# cartridge.net
KiCad netlist of a schematic drawn in EasyEDA Pro
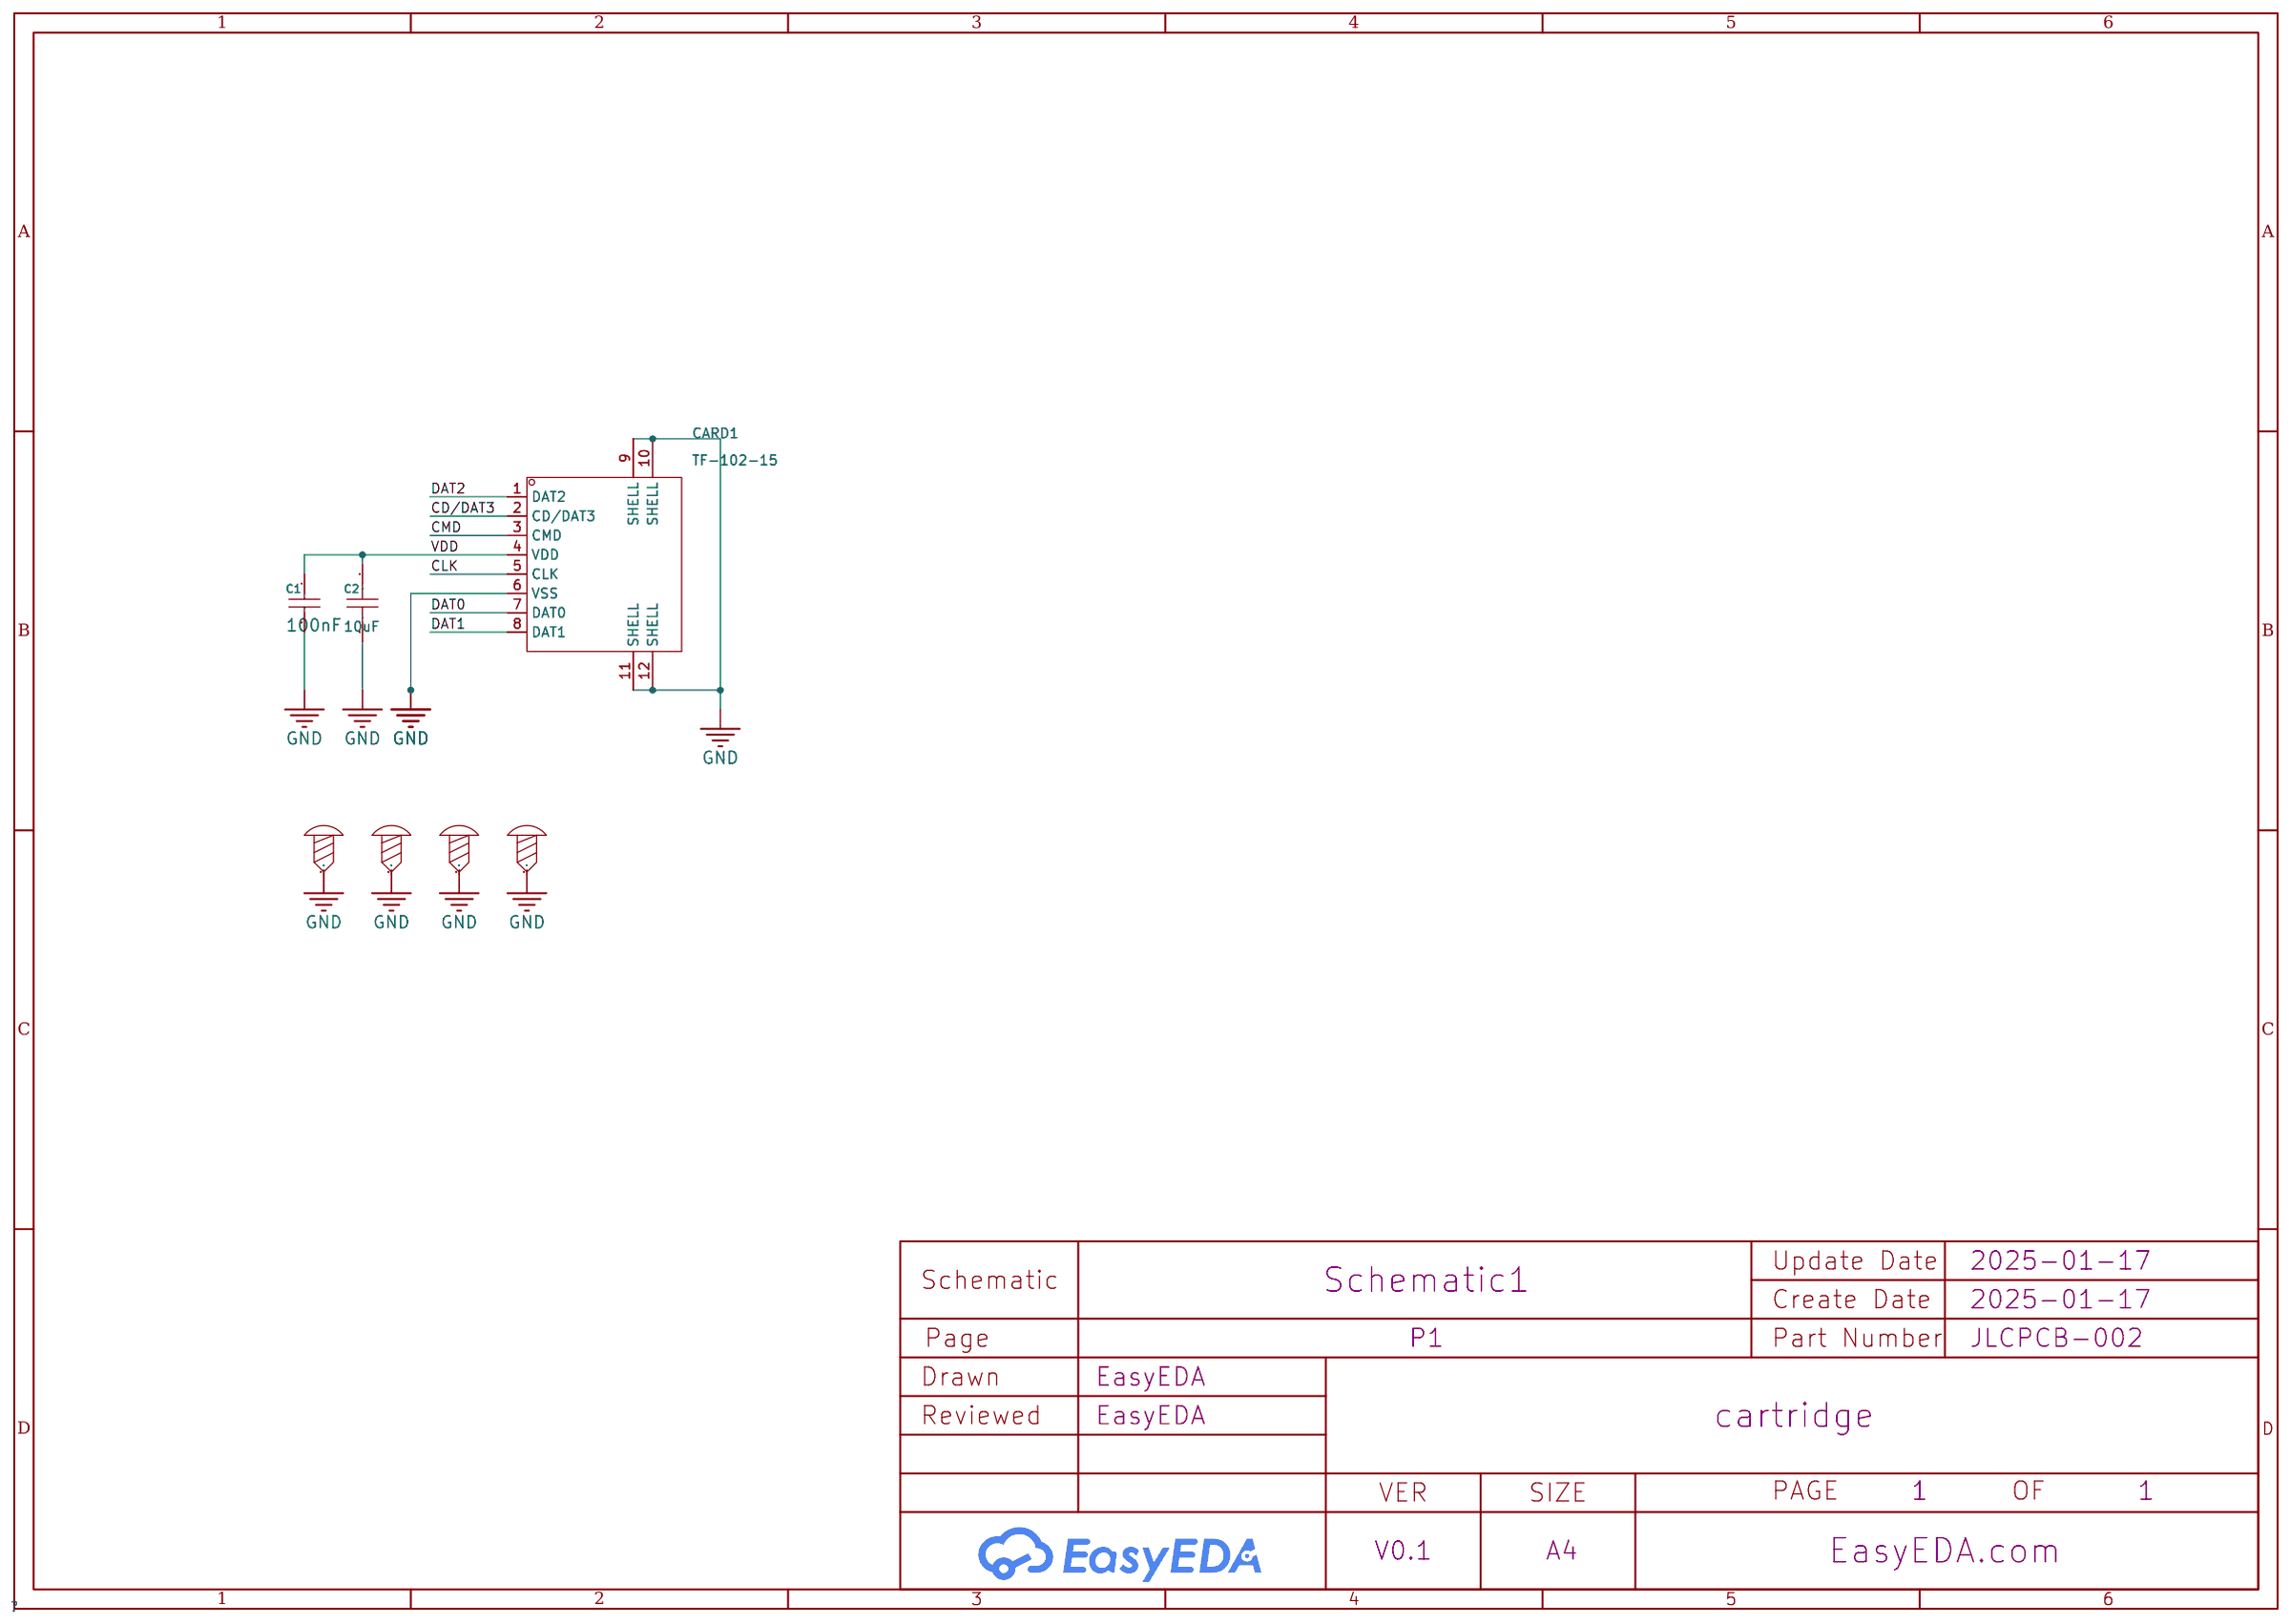
[diagram p0: schematic sheet]

(export (version "E")
  (design (tool "Eeschema 10.0.6"))
  (components
    (comp (ref "C1")
      (value "100nF")
      (footprint "easyedapro:C0805")
      (fields
        (field (name "Manufacturer Part") "CL21B104KBCNNNC")
        (field (name "Manufacturer") "SAMSUNG(三星)")
      )
      (libsource (lib "easyedapro") (part "CL21B104KBCNNNC"))
    )
    (comp (ref "C2")
      (value "10uF")
      (footprint "easyedapro:C0805")
      (fields
        (field (name "Manufacturer Part") "CL21A106KAYNNNE")
        (field (name "Manufacturer") "SAMSUNG(三星)")
      )
      (libsource (lib "easyedapro") (part "CL21A106KAYNNNE"))
    )
    (comp (ref "CARD1")
      (value "TF-102-15")
      (footprint "easyedapro:TF-SMD_TF-102-15")
      (fields (field (name "Manufacturer") "XUNPU(讯普)"))
      (libsource (lib "easyedapro") (part "TF-102-15"))
    )
    (comp (ref "SCREW1")
      (value "~")
      (footprint "easyedapro:Screw-Hole-M2")
      (libsource (lib "easyedapro") (part "Screw-Hole"))
    )
    (comp (ref "SCREW2")
      (value "~")
      (footprint "easyedapro:Screw-Hole-M2")
      (libsource (lib "easyedapro") (part "Screw-Hole"))
    )
    (comp (ref "SCREW3")
      (value "~")
      (footprint "easyedapro:Screw-Hole-M2")
      (libsource (lib "easyedapro") (part "Screw-Hole"))
    )
    (comp (ref "SCREW4")
      (value "~")
      (footprint "easyedapro:Screw-Hole-M2")
      (libsource (lib "easyedapro") (part "Screw-Hole"))
    )
  )
  (nets
    (net (code "1") (name "/CD{slash}DAT3") (class "Default")
      (node (ref "CARD1") (pin "2") (pinfunction "CD/DAT3_2") (pintype "unspecified"))
    )
    (net (code "2") (name "/CLK") (class "Default")
      (node (ref "CARD1") (pin "5") (pinfunction "CLK_5") (pintype "unspecified"))
    )
    (net (code "3") (name "/CMD") (class "Default")
      (node (ref "CARD1") (pin "3") (pinfunction "CMD_3") (pintype "unspecified"))
    )
    (net (code "4") (name "/DAT0") (class "Default")
      (node (ref "CARD1") (pin "7") (pinfunction "DAT0_7") (pintype "unspecified"))
    )
    (net (code "5") (name "/DAT1") (class "Default")
      (node (ref "CARD1") (pin "8") (pinfunction "DAT1_8") (pintype "unspecified"))
    )
    (net (code "6") (name "/DAT2") (class "Default")
      (node (ref "CARD1") (pin "1") (pinfunction "DAT2_1") (pintype "unspecified"))
    )
    (net (code "7") (name "/VDD") (class "Default")
      (node (ref "C1") (pin "1") (pinfunction "1_1") (pintype "input"))
      (node (ref "C2") (pin "2") (pinfunction "2_2") (pintype "unspecified"))
      (node (ref "CARD1") (pin "4") (pinfunction "VDD_4") (pintype "unspecified"))
    )
    (net (code "8") (name "GND") (class "Default")
      (node (ref "C1") (pin "2") (pinfunction "2_2") (pintype "input"))
      (node (ref "C2") (pin "1") (pinfunction "1_1") (pintype "unspecified"))
      (node (ref "CARD1") (pin "10") (pinfunction "SHELL_10") (pintype "unspecified"))
      (node (ref "CARD1") (pin "11") (pinfunction "SHELL_11") (pintype "unspecified"))
      (node (ref "CARD1") (pin "12") (pinfunction "SHELL_12") (pintype "unspecified"))
      (node (ref "CARD1") (pin "6") (pinfunction "VSS_6") (pintype "unspecified"))
      (node (ref "CARD1") (pin "9") (pinfunction "SHELL_9") (pintype "unspecified"))
      (node (ref "SCREW1") (pin "1") (pinfunction "1_1") (pintype "input"))
      (node (ref "SCREW2") (pin "1") (pinfunction "1_1") (pintype "input"))
      (node (ref "SCREW3") (pin "1") (pinfunction "1_1") (pintype "input"))
      (node (ref "SCREW4") (pin "1") (pinfunction "1_1") (pintype "input"))
    )
  )
)
